# ProProject_Strain_Gauge_Paddle_2024-04-2.net
KiCad netlist of a schematic drawn in EasyEDA Pro
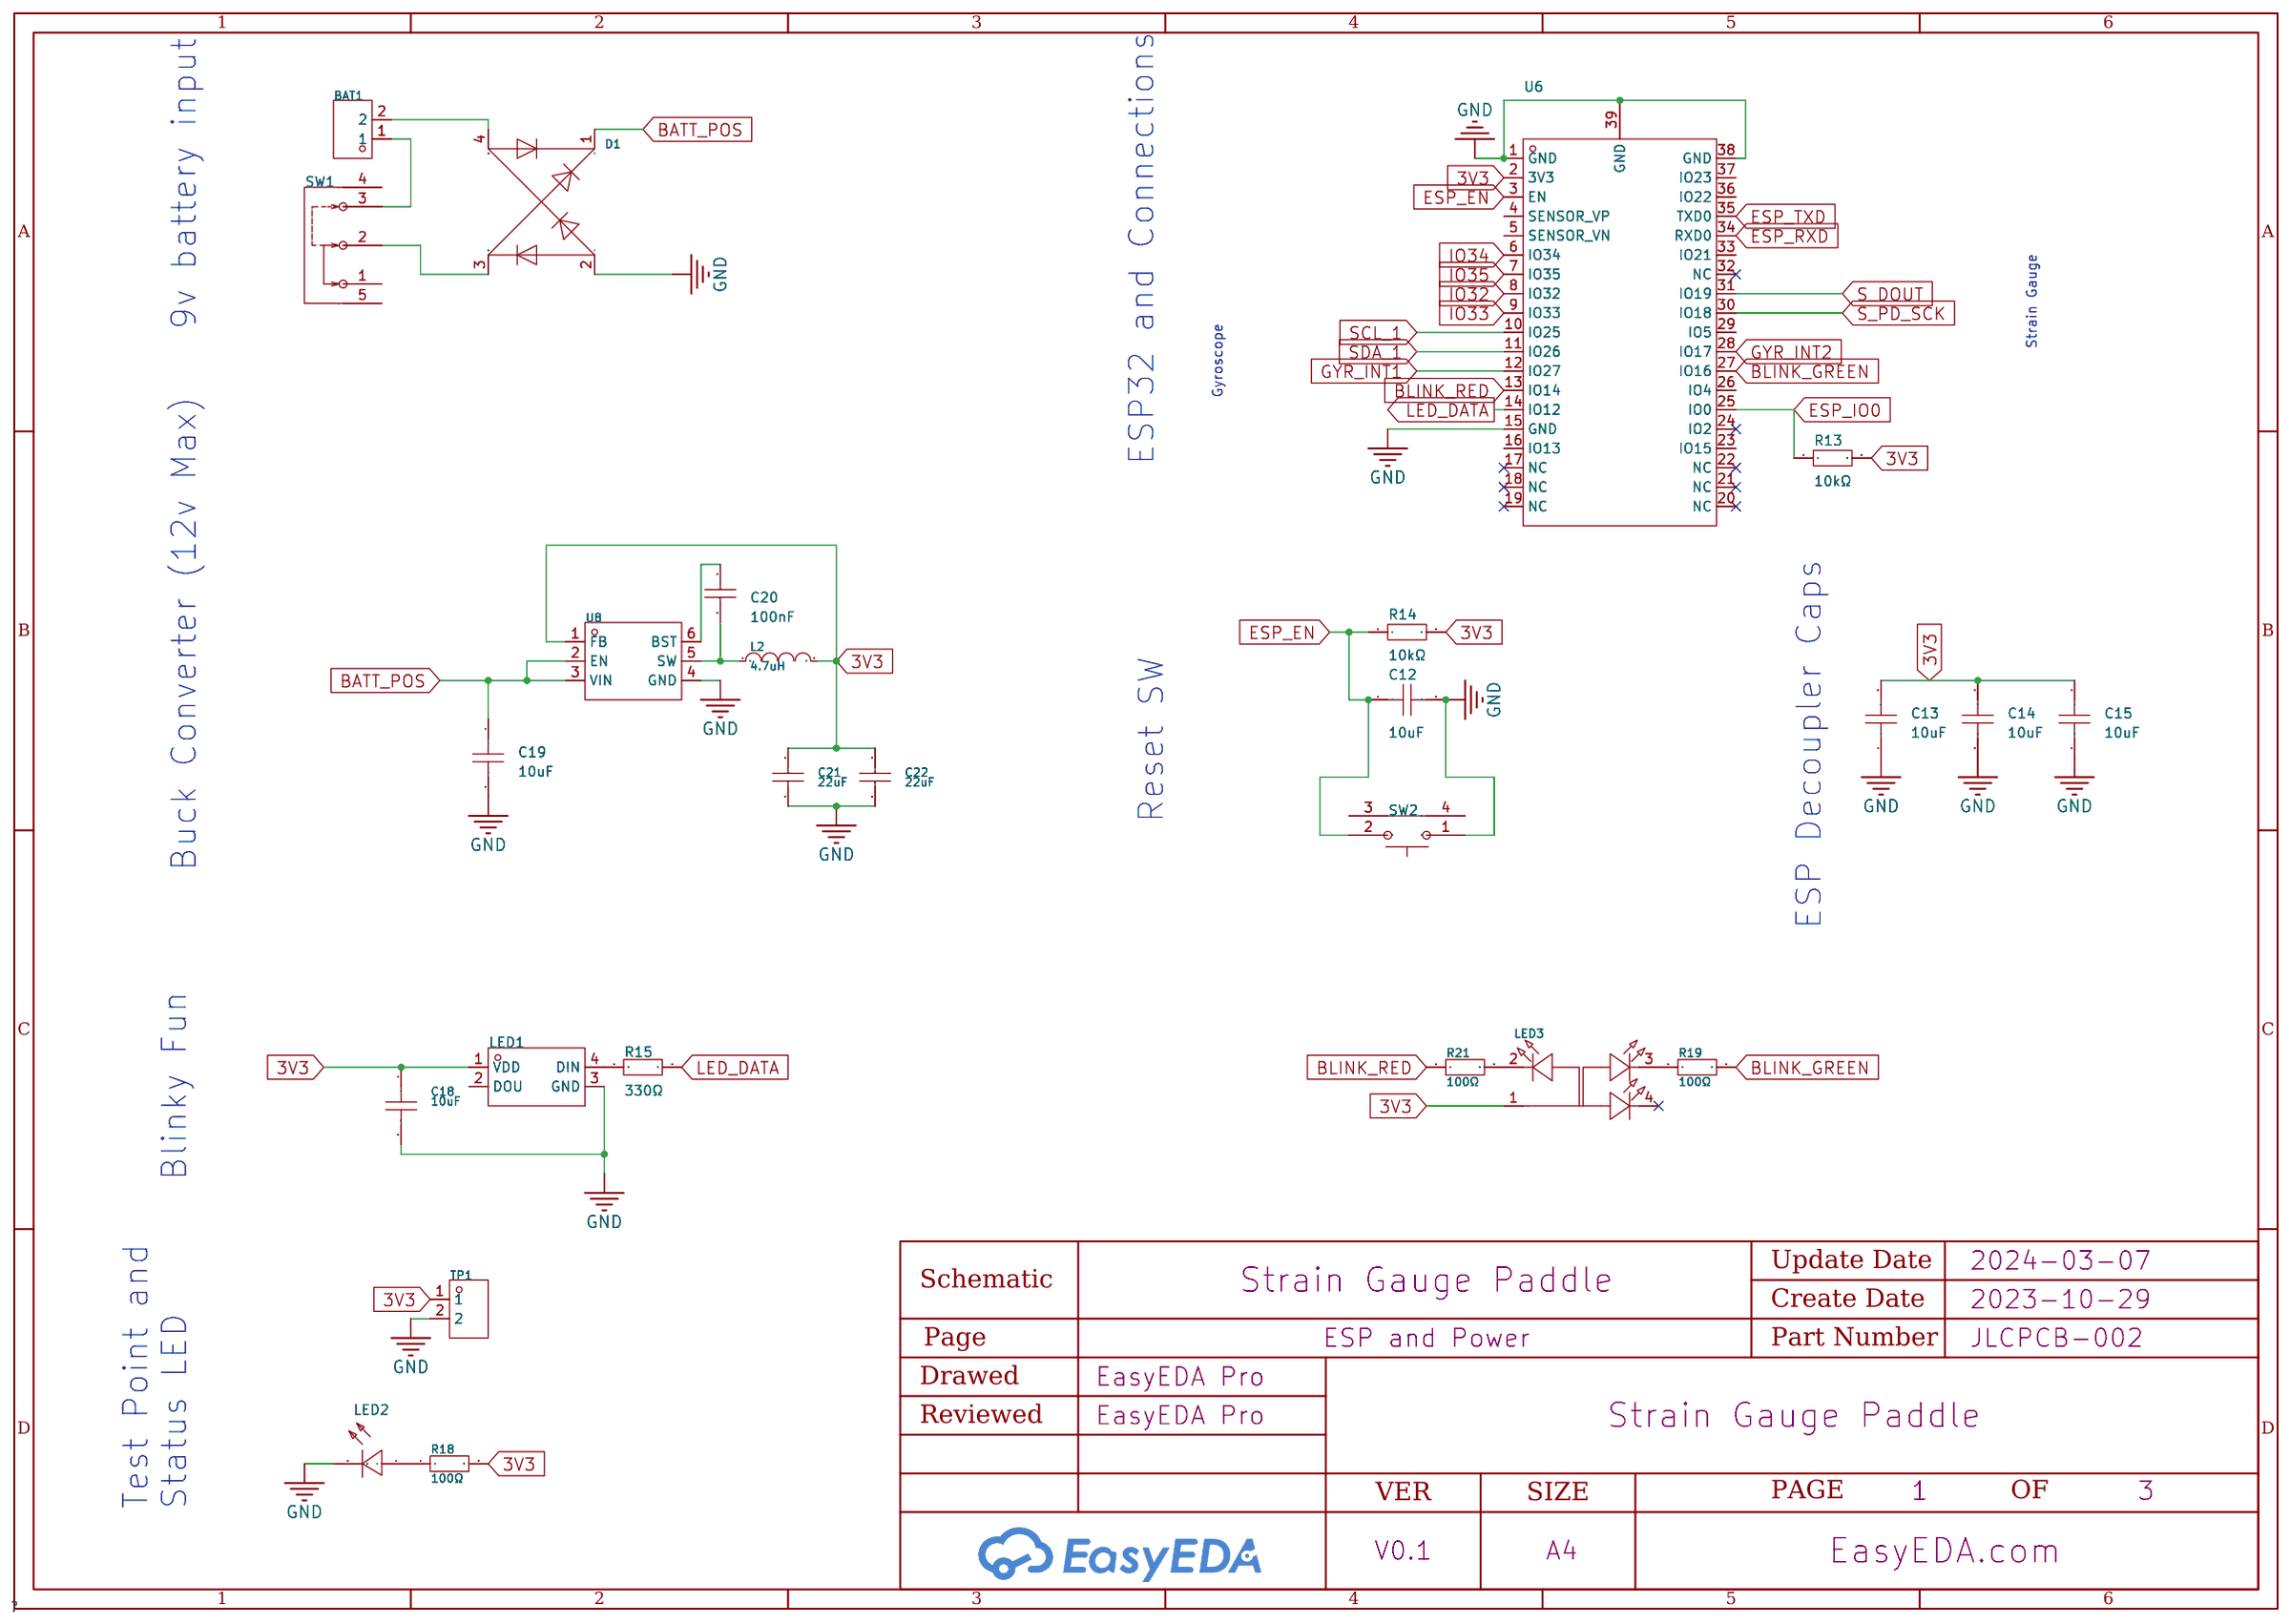
[diagram p0: ESP and Power]
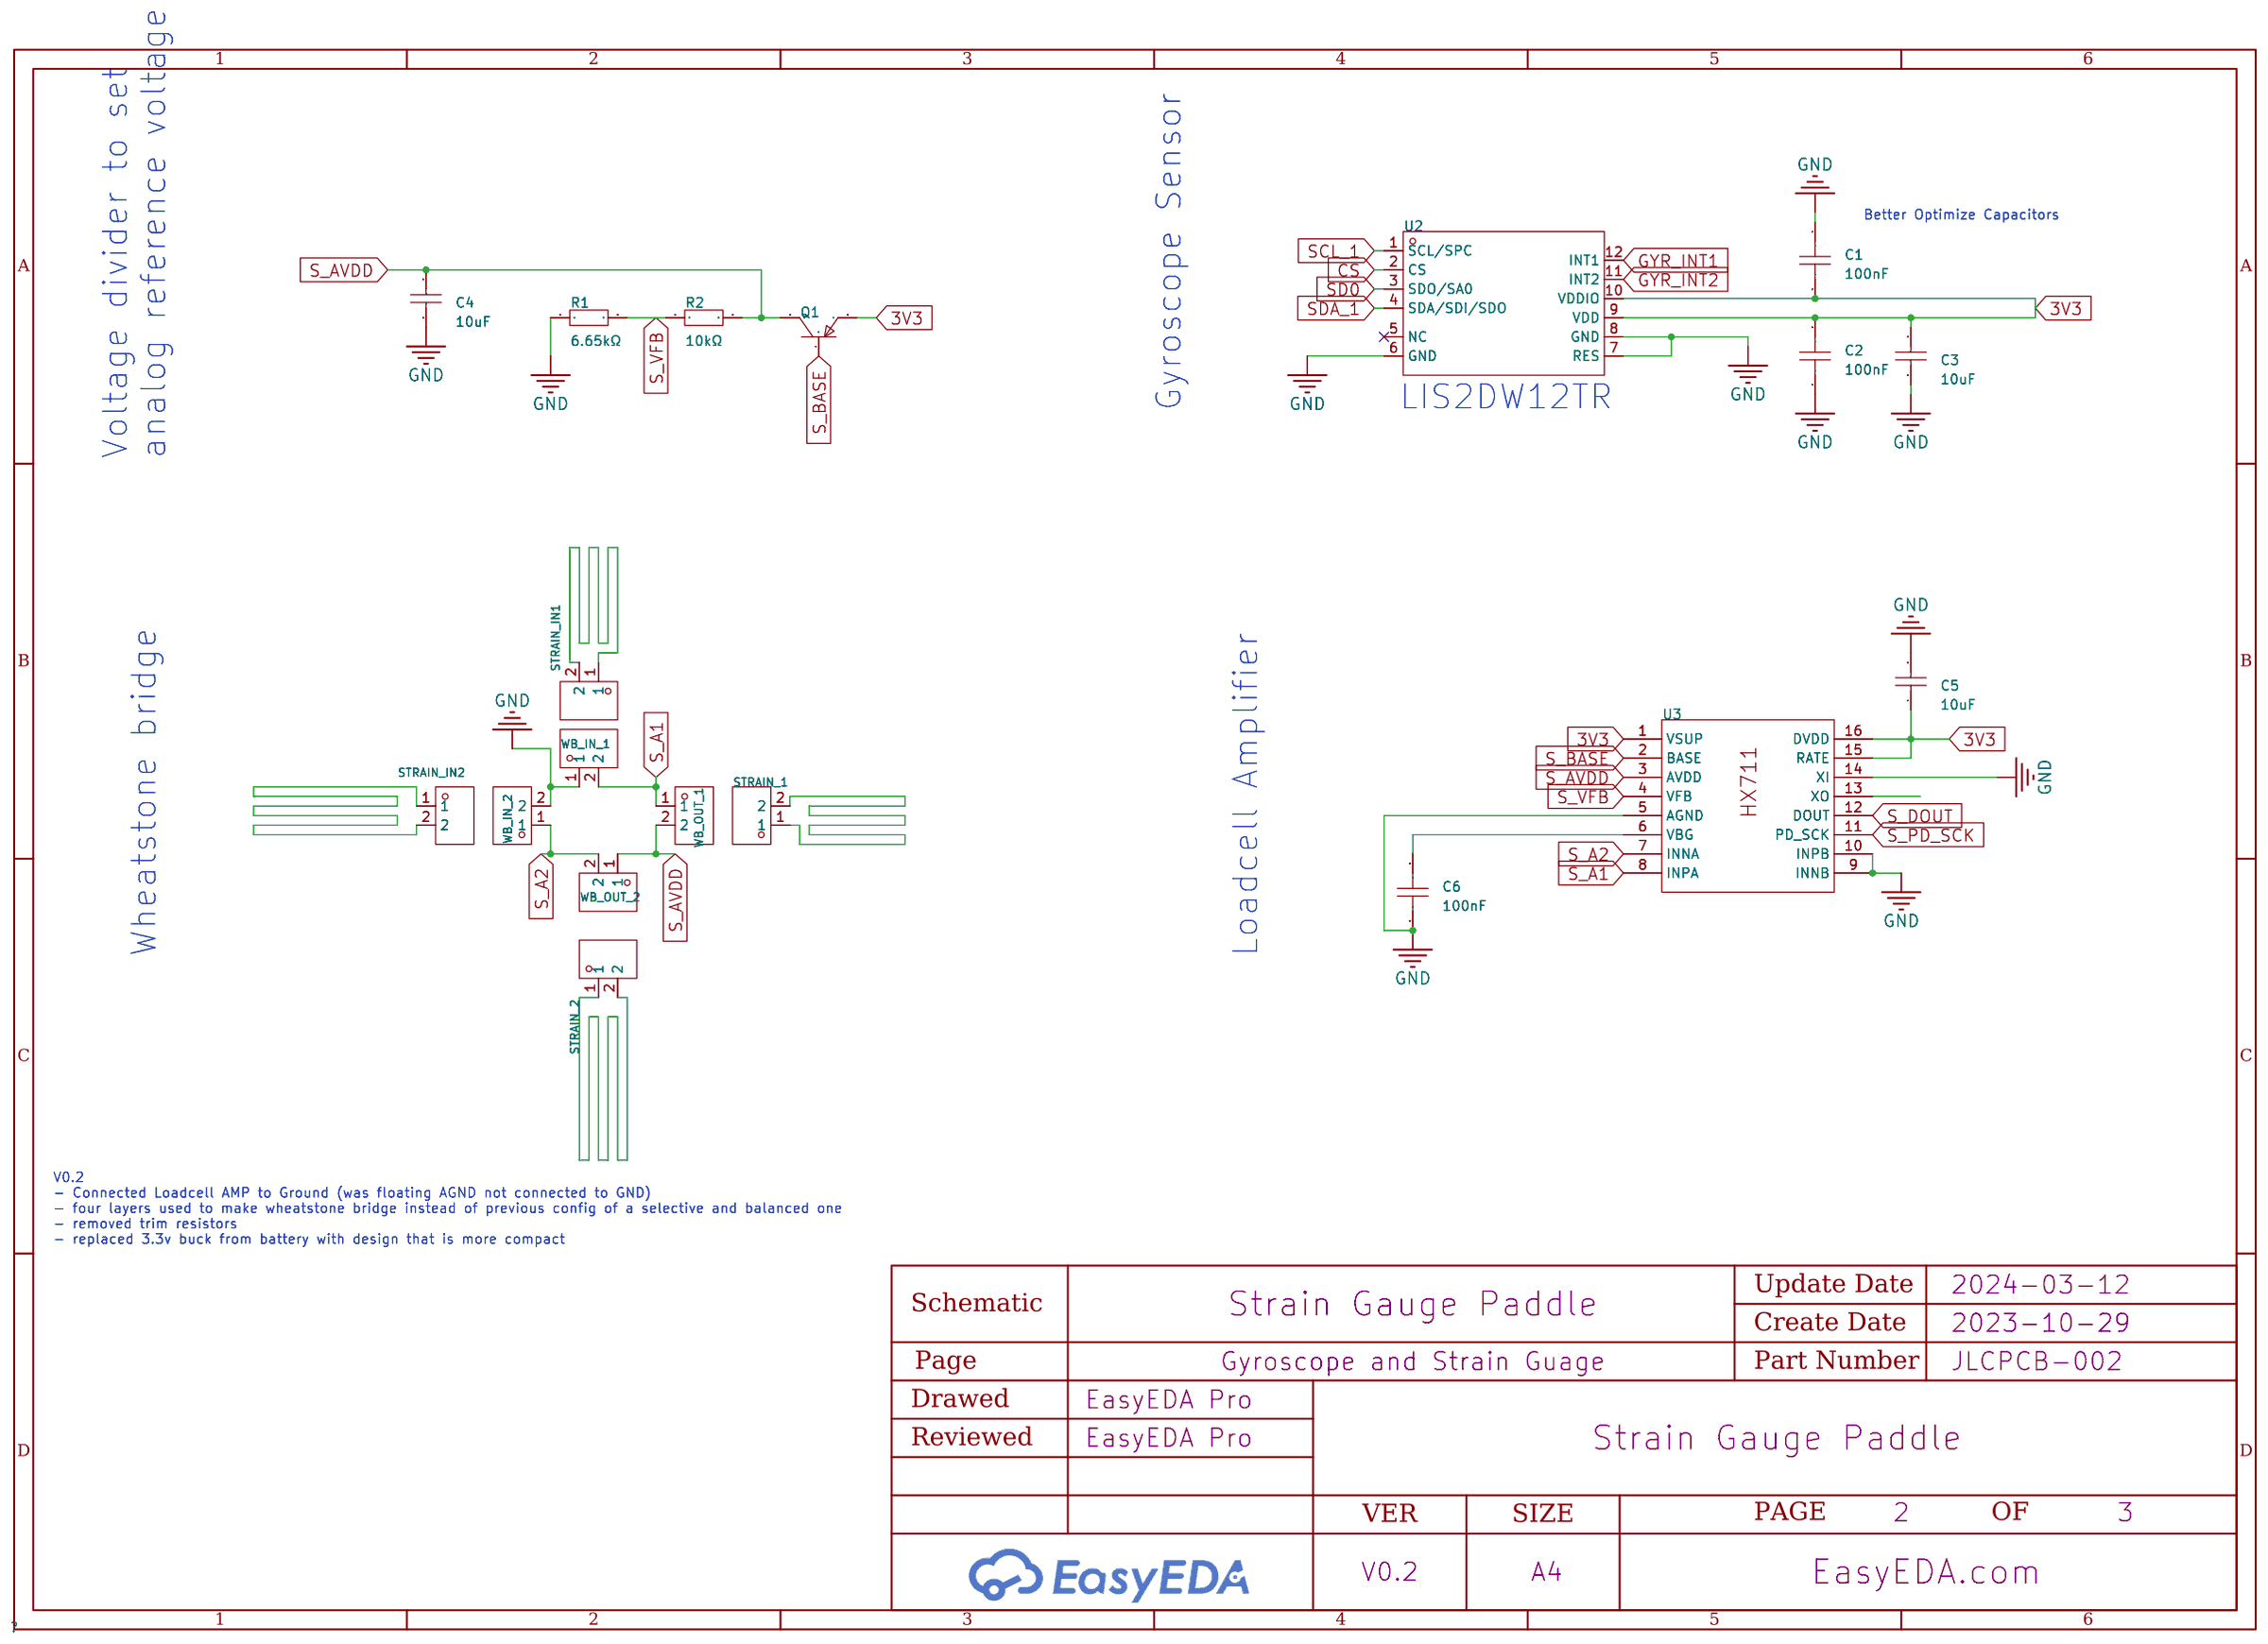
[diagram p1: Gyroscope and Strain Guage]
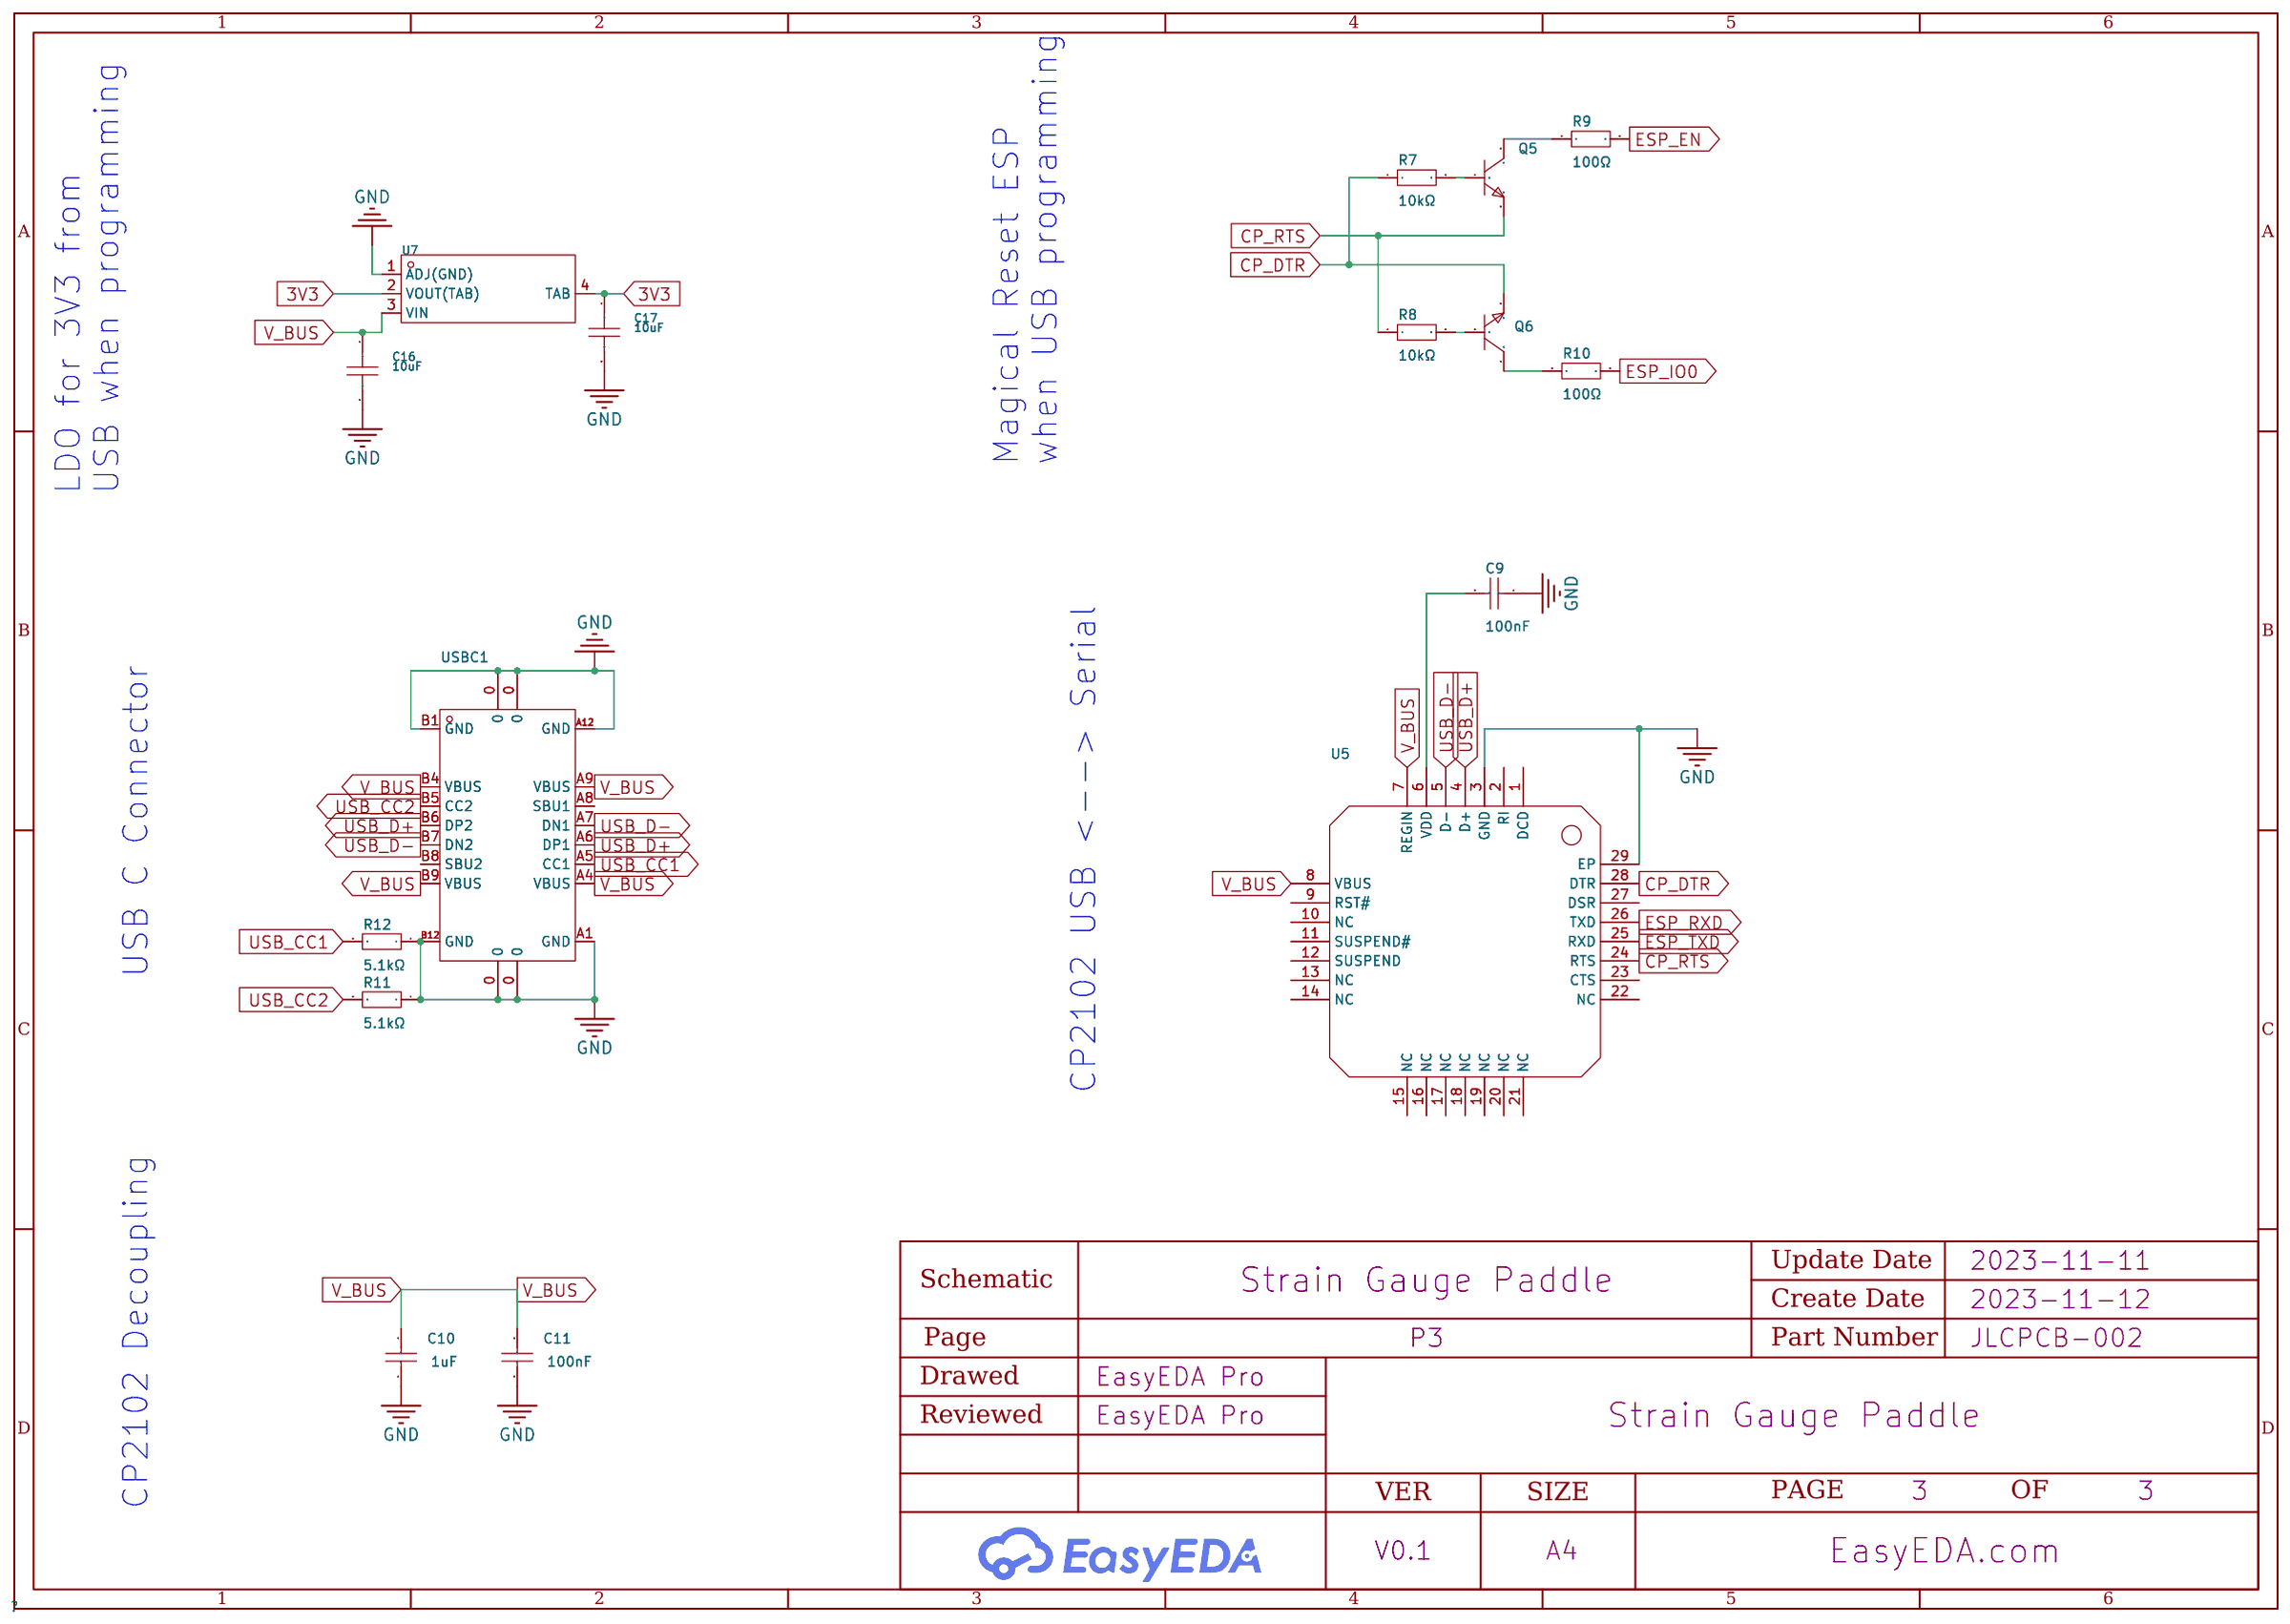
[diagram p2: Serial]

(export (version "E")
  (design (tool "Eeschema 10.0.6"))
  (components
    (comp (ref "BAT1")
      (value "PZ254V-11-02P")
      (footprint "easyedapro:HDR-TH_2P-P2.54-V-M")
      (fields (field (name "Manufacturer") "XFCN(兴飞)"))
      (libsource (lib "easyedapro") (part "PZ254V-11-02P"))
    )
    (comp (ref "C12")
      (value "10uF")
      (footprint "easyedapro:C0402")
      (description "Capacitance:10uF Tolerance:±20% Tolerance:±20% Voltage Rated:10V Temperature Coefficient:X5R")
      (fields
        (field (name "Manufacturer Part") "GRM155R61A106ME44D")
        (field (name "Manufacturer") "muRata(村田)")
      )
      (libsource (lib "easyedapro") (part "GRM155R61A106ME44D"))
    )
    (comp (ref "C13")
      (value "10uF")
      (footprint "easyedapro:C0402")
      (description "Capacitance:10uF Tolerance:±20% Tolerance:±20% Voltage Rated:10V Temperature Coefficient:X5R")
      (fields
        (field (name "Manufacturer Part") "GRM155R61A106ME44D")
        (field (name "Manufacturer") "muRata(村田)")
      )
      (libsource (lib "easyedapro") (part "GRM155R61A106ME44D"))
    )
    (comp (ref "C14")
      (value "10uF")
      (footprint "easyedapro:C0402")
      (description "Capacitance:10uF Tolerance:±20% Tolerance:±20% Voltage Rated:10V Temperature Coefficient:X5R")
      (fields
        (field (name "Manufacturer Part") "GRM155R61A106ME44D")
        (field (name "Manufacturer") "muRata(村田)")
      )
      (libsource (lib "easyedapro") (part "GRM155R61A106ME44D"))
    )
    (comp (ref "C15")
      (value "10uF")
      (footprint "easyedapro:C0402")
      (description "Capacitance:10uF Tolerance:±20% Tolerance:±20% Voltage Rated:10V Temperature Coefficient:X5R")
      (fields
        (field (name "Manufacturer Part") "GRM155R61A106ME44D")
        (field (name "Manufacturer") "muRata(村田)")
      )
      (libsource (lib "easyedapro") (part "GRM155R61A106ME44D"))
    )
    (comp (ref "C18")
      (value "10uF")
      (footprint "easyedapro:C0603")
      (fields
        (field (name "Manufacturer Part") "CL10A106MQ8NNNC")
        (field (name "Manufacturer") "SAMSUNG(三星)")
      )
      (libsource (lib "easyedapro") (part "CL10A106MQ8NNNC"))
    )
    (comp (ref "C19")
      (value "10uF")
      (footprint "easyedapro:C0603")
      (fields
        (field (name "Manufacturer Part") "CL10A106KP8NNNC")
        (field (name "Manufacturer") "SAMSUNG(三星)")
      )
      (libsource (lib "easyedapro") (part "CL10A106KP8NNNC"))
    )
    (comp (ref "C20")
      (value "100nF")
      (footprint "easyedapro:C0603")
      (fields (field (name "Manufacturer Part") "0603B104K500NT") (field (name "Manufacturer") "FH(风华)"))
      (libsource (lib "easyedapro") (part "0603B104K500NT"))
    )
    (comp (ref "C21")
      (value "22uF")
      (footprint "easyedapro:C1206")
      (fields
        (field (name "Manufacturer Part") "CL31A226KAHNNNE")
        (field (name "Manufacturer") "SAMSUNG(三星)")
      )
      (libsource (lib "easyedapro") (part "CL31A226KAHNNNE"))
    )
    (comp (ref "C22")
      (value "22uF")
      (footprint "easyedapro:C1206")
      (fields
        (field (name "Manufacturer Part") "CL31A226KAHNNNE")
        (field (name "Manufacturer") "SAMSUNG(三星)")
      )
      (libsource (lib "easyedapro") (part "CL31A226KAHNNNE"))
    )
    (comp (ref "D1")
      (value "MB10S")
      (footprint "easyedapro:MBS_L4.7-W3.8-P2.40-LS7.0-TL")
      (fields (field (name "Manufacturer") "MDD"))
      (libsource (lib "easyedapro") (part "MB10S_C2488"))
    )
    (comp (ref "L2")
      (value "4.7uH")
      (footprint "easyedapro:IND-SMD_L5.4-W5.2_FXL0530")
      (fields (field (name "Manufacturer Part") "FXL0530-4R7-M") (field (name "Manufacturer") "cjiang(长江微电)"))
      (libsource (lib "easyedapro") (part "FXL0530-4R7-M"))
    )
    (comp (ref "LED1")
      (value "XL-5050RGBC-WS2812B")
      (footprint "easyedapro:LED-SMD_4P-L5.0-W5.0-BL_XL-5050RGBC")
      (fields (field (name "Manufacturer") "XINGLIGHT(成兴光)"))
      (libsource (lib "easyedapro") (part "XL-5050RGBC-WS2812B"))
    )
    (comp (ref "LED2")
      (value "BL-HJC36G-AV-TRB")
      (footprint "easyedapro:LED0603-R-RD_AMBER")
      (fields (field (name "Manufacturer") "BrtLed(佰鸿)"))
      (libsource (lib "easyedapro") (part "BL-HJC36G-AV-TRB"))
    )
    (comp (ref "LED3")
      (value "NH-B1010RGBT-HF")
      (footprint "easyedapro:LED-ARRAY-SMD_4P-L1.0-W1.0-TR_NH-B1010RGBT")
      (fields (field (name "Manufacturer") "国星光电"))
      (libsource (lib "easyedapro") (part "NH-B1010RGBT-HF"))
    )
    (comp (ref "R13")
      (value "10kΩ")
      (footprint "easyedapro:R0402")
      (fields (field (name "Manufacturer Part") "WR04X1002FTL") (field (name "Manufacturer") "华新科(Walsin)"))
      (libsource (lib "easyedapro") (part "WR04X1002FTL"))
    )
    (comp (ref "R14")
      (value "10kΩ")
      (footprint "easyedapro:R0402")
      (fields (field (name "Manufacturer Part") "WR04X1002FTL") (field (name "Manufacturer") "华新科(Walsin)"))
      (libsource (lib "easyedapro") (part "WR04X1002FTL"))
    )
    (comp (ref "R15")
      (value "330Ω")
      (footprint "easyedapro:R0603")
      (fields
        (field (name "Manufacturer Part") "0603WAF3300T5E")
        (field (name "Manufacturer") "UNI-ROYAL(厚声)")
      )
      (libsource (lib "easyedapro") (part "0603WAF3300T5E"))
    )
    (comp (ref "R18")
      (value "100Ω")
      (footprint "easyedapro:R0603")
      (fields
        (field (name "Manufacturer Part") "0603WAF1000T5E")
        (field (name "Manufacturer") "UNI-ROYAL(厚声)")
      )
      (libsource (lib "easyedapro") (part "0603WAF1000T5E"))
    )
    (comp (ref "R19")
      (value "100Ω")
      (footprint "easyedapro:R0603")
      (fields
        (field (name "Manufacturer Part") "0603WAF1000T5E")
        (field (name "Manufacturer") "UNI-ROYAL(厚声)")
      )
      (libsource (lib "easyedapro") (part "0603WAF1000T5E"))
    )
    (comp (ref "R21")
      (value "100Ω")
      (footprint "easyedapro:R0603")
      (fields
        (field (name "Manufacturer Part") "0603WAF1000T5E")
        (field (name "Manufacturer") "UNI-ROYAL(厚声)")
      )
      (libsource (lib "easyedapro") (part "0603WAF1000T5E"))
    )
    (comp (ref "SW1")
      (value "SK12D07VG4")
      (footprint "easyedapro:SW-TH_SK12D07VG4")
      (fields (field (name "Manufacturer") "SHOU HAN(首韩)"))
      (libsource (lib "easyedapro") (part "SK12D07VG4"))
    )
    (comp (ref "SW2")
      (value "1TS003B-1400-3500A-CT")
      (footprint "easyedapro:KEY-SMD_1TS003B")
      (fields (field (name "Manufacturer") "HYP(鸿源精密)"))
      (libsource (lib "easyedapro") (part "1TS003B-1400-3500A"))
    )
    (comp (ref "TP1")
      (value "PZ254V-11-02P")
      (footprint "easyedapro:HDR-TH_2P-P2.54-V-M")
      (fields (field (name "Manufacturer") "XFCN(兴飞)"))
      (libsource (lib "easyedapro") (part "PZ254V-11-02P"))
    )
    (comp (ref "U6")
      (value "~")
      (footprint "easyedapro:WIFI-SMD_ESP32-WROOM-32E")
      (fields
        (field (name "Manufacturer Part") "ESP32-WROOM-32E(8MB)")
        (field (name "Manufacturer") "ESPRESSIF 乐鑫")
      )
      (libsource (lib "easyedapro") (part "ESP32-WROOM-32E(8MB)"))
    )
    (comp (ref "U8")
      (value "AP63203WU-7")
      (footprint "easyedapro:TSOT-26_L2.9-W1.6-P0.95-LS2.8-BL")
      (fields (field (name "Manufacturer") "DIODES(美台)"))
      (libsource (lib "easyedapro") (part "AP63203WU-7"))
    )
    (comp (ref "C1")
      (value "100nF")
      (footprint "easyedapro:C0603")
      (fields
        (field (name "Manufacturer Part") "CC0603KRX7R9BB104")
        (field (name "Manufacturer") "YAGEO(国巨)")
      )
      (libsource (lib "easyedapro") (part "CC0603KRX7R9BB104"))
    )
    (comp (ref "C2")
      (value "100nF")
      (footprint "easyedapro:C0603")
      (fields
        (field (name "Manufacturer Part") "CC0603KRX7R9BB104")
        (field (name "Manufacturer") "YAGEO(国巨)")
      )
      (libsource (lib "easyedapro") (part "CC0603KRX7R9BB104"))
    )
    (comp (ref "C3")
      (value "10uF")
      (footprint "easyedapro:C0805")
      (fields
        (field (name "Manufacturer Part") "CL21A106KAYNNNE")
        (field (name "Manufacturer") "SAMSUNG(三星)")
      )
      (libsource (lib "easyedapro") (part "CL21A106KAYNNNE"))
    )
    (comp (ref "C4")
      (value "10uF")
      (footprint "easyedapro:C0805")
      (fields
        (field (name "Manufacturer Part") "CL21A106KAYNNNE")
        (field (name "Manufacturer") "SAMSUNG(三星)")
      )
      (libsource (lib "easyedapro") (part "CL21A106KAYNNNE"))
    )
    (comp (ref "C5")
      (value "10uF")
      (footprint "easyedapro:C0805")
      (fields
        (field (name "Manufacturer Part") "CL21A106KAYNNNE")
        (field (name "Manufacturer") "SAMSUNG(三星)")
      )
      (libsource (lib "easyedapro") (part "CL21A106KAYNNNE"))
    )
    (comp (ref "C6")
      (value "100nF")
      (footprint "easyedapro:C0603")
      (fields
        (field (name "Manufacturer Part") "CC0603KRX7R9BB104")
        (field (name "Manufacturer") "YAGEO(国巨)")
      )
      (libsource (lib "easyedapro") (part "CC0603KRX7R9BB104"))
    )
    (comp (ref "Q1")
      (value "S8550")
      (footprint "easyedapro:SOT-23-3_L2.9-W1.3-P1.90-LS2.4-BR")
      (fields (field (name "Manufacturer") "YONGYUTAI(永裕泰)"))
      (libsource (lib "easyedapro") (part "S8550_C2891805"))
    )
    (comp (ref "R1")
      (value "6.65kΩ")
      (footprint "easyedapro:R0603")
      (fields
        (field (name "Manufacturer Part") "0603WAF6651T5E")
        (field (name "Manufacturer") "UNI-ROYAL(厚声)")
      )
      (libsource (lib "easyedapro") (part "0603WAF6651T5E"))
    )
    (comp (ref "R2")
      (value "10kΩ")
      (footprint "easyedapro:R0805")
      (fields
        (field (name "Manufacturer Part") "0805W8F1002T5E")
        (field (name "Manufacturer") "UNI-ROYAL(厚声)")
      )
      (libsource (lib "easyedapro") (part "0805W8F1002T5E"))
    )
    (comp (ref "STRAIN_1")
      (value "PZ254V-11-02P")
      (footprint "easyedapro:HDR-TH_2P-P2.54-V-M")
      (fields (field (name "Manufacturer") "XFCN(兴飞)"))
      (libsource (lib "easyedapro") (part "PZ254V-11-02P"))
    )
    (comp (ref "STRAIN_2")
      (value "PZ254V-11-02P")
      (footprint "easyedapro:HDR-TH_2P-P2.54-V-M")
      (fields (field (name "Manufacturer") "XFCN(兴飞)"))
      (libsource (lib "easyedapro") (part "PZ254V-11-02P"))
    )
    (comp (ref "STRAIN_IN1")
      (value "PZ254V-11-02P")
      (footprint "easyedapro:HDR-TH_2P-P2.54-V-M")
      (fields (field (name "Manufacturer") "XFCN(兴飞)"))
      (libsource (lib "easyedapro") (part "PZ254V-11-02P"))
    )
    (comp (ref "STRAIN_IN2")
      (value "PZ254V-11-02P")
      (footprint "easyedapro:HDR-TH_2P-P2.54-V-M")
      (fields (field (name "Manufacturer") "XFCN(兴飞)"))
      (libsource (lib "easyedapro") (part "PZ254V-11-02P"))
    )
    (comp (ref "U2")
      (value "LIS2DW12TR")
      (footprint "easyedapro:LGA-12_L2.0-W2.0-P0.50-BL")
      (fields (field (name "Manufacturer") "ST(意法半导体)"))
      (libsource (lib "easyedapro") (part "LIS2DW12TR"))
    )
    (comp (ref "U3")
      (value "HX711")
      (footprint "easyedapro:SOP-16_L10.0-W3.9-P1.27-LS6.0-BL")
      (fields (field (name "Manufacturer") "AVIA(海芯科技)"))
      (libsource (lib "easyedapro") (part "HX711"))
    )
    (comp (ref "WB_IN_1")
      (value "PZ254V-11-02P")
      (footprint "easyedapro:HDR-TH_2P-P2.54-V-M")
      (fields (field (name "Manufacturer") "XFCN(兴飞)"))
      (libsource (lib "easyedapro") (part "PZ254V-11-02P"))
    )
    (comp (ref "WB_IN_2")
      (value "PZ254V-11-02P")
      (footprint "easyedapro:HDR-TH_2P-P2.54-V-M")
      (fields (field (name "Manufacturer") "XFCN(兴飞)"))
      (libsource (lib "easyedapro") (part "PZ254V-11-02P"))
    )
    (comp (ref "WB_OUT_1")
      (value "PZ254V-11-02P")
      (footprint "easyedapro:HDR-TH_2P-P2.54-V-M")
      (fields (field (name "Manufacturer") "XFCN(兴飞)"))
      (libsource (lib "easyedapro") (part "PZ254V-11-02P"))
    )
    (comp (ref "WB_OUT_2")
      (value "PZ254V-11-02P")
      (footprint "easyedapro:HDR-TH_2P-P2.54-V-M")
      (fields (field (name "Manufacturer") "XFCN(兴飞)"))
      (libsource (lib "easyedapro") (part "PZ254V-11-02P"))
    )
    (comp (ref "C9")
      (value "100nF")
      (footprint "easyedapro:C0402")
      (description "Capacitance:100nF Tolerance:±10% Tolerance:±10% Voltage Rated:25V Temperature Coefficient:X5R")
      (fields (field (name "Manufacturer Part") "0402X104K250CT") (field (name "Manufacturer") "华新科(Walsin)"))
      (libsource (lib "easyedapro") (part "0402X104K250CT"))
    )
    (comp (ref "C10")
      (value "1uF")
      (footprint "easyedapro:C0402")
      (description "Capacitance:1uF Tolerance:±10% Tolerance:±10% Voltage Rated:25V Temperature Coefficient:X5R")
      (fields
        (field (name "Manufacturer Part") "GRM155R61E105KA12D")
        (field (name "Manufacturer") "muRata(村田)")
      )
      (libsource (lib "easyedapro") (part "GRM155R61E105KA12D"))
    )
    (comp (ref "C11")
      (value "100nF")
      (footprint "easyedapro:C0402")
      (description "Capacitance:100nF Tolerance:±10% Tolerance:±10% Voltage Rated:25V Temperature Coefficient:X5R")
      (fields (field (name "Manufacturer Part") "0402X104K250CT") (field (name "Manufacturer") "华新科(Walsin)"))
      (libsource (lib "easyedapro") (part "0402X104K250CT"))
    )
    (comp (ref "C16")
      (value "10uF")
      (footprint "easyedapro:C0603")
      (fields
        (field (name "Manufacturer Part") "CL10A106MQ8NNNC")
        (field (name "Manufacturer") "SAMSUNG(三星)")
      )
      (libsource (lib "easyedapro") (part "CL10A106MQ8NNNC"))
    )
    (comp (ref "C17")
      (value "10uF")
      (footprint "easyedapro:C0603")
      (fields
        (field (name "Manufacturer Part") "CL10A106MQ8NNNC")
        (field (name "Manufacturer") "SAMSUNG(三星)")
      )
      (libsource (lib "easyedapro") (part "CL10A106MQ8NNNC"))
    )
    (comp (ref "Q5")
      (value "~")
      (footprint "easyedapro:SOT-23-3_L2.9-W1.3-P1.90-LS2.4-BR")
      (fields (field (name "Manufacturer Part") "BC817") (field (name "Manufacturer") "CJ（江苏长电/长晶）"))
      (libsource (lib "easyedapro") (part "BC817-16 6A"))
    )
    (comp (ref "Q6")
      (value "~")
      (footprint "easyedapro:SOT-23-3_L2.9-W1.3-P1.90-LS2.4-BR")
      (fields (field (name "Manufacturer Part") "BC817") (field (name "Manufacturer") "CJ（江苏长电/长晶）"))
      (libsource (lib "easyedapro") (part "BC817-16 6A"))
    )
    (comp (ref "R7")
      (value "10kΩ")
      (footprint "easyedapro:R0402")
      (fields (field (name "Manufacturer Part") "WR04X1002FTL") (field (name "Manufacturer") "华新科(Walsin)"))
      (libsource (lib "easyedapro") (part "WR04X1002FTL"))
    )
    (comp (ref "R8")
      (value "10kΩ")
      (footprint "easyedapro:R0402")
      (fields (field (name "Manufacturer Part") "WR04X1002FTL") (field (name "Manufacturer") "华新科(Walsin)"))
      (libsource (lib "easyedapro") (part "WR04X1002FTL"))
    )
    (comp (ref "R9")
      (value "100Ω")
      (footprint "easyedapro:R0402")
      (fields (field (name "Manufacturer Part") "AECR0402F100RK9") (field (name "Manufacturer") "RESI(开步睿思）"))
      (libsource (lib "easyedapro") (part "AECR0402F100RK9"))
    )
    (comp (ref "R10")
      (value "100Ω")
      (footprint "easyedapro:R0402")
      (fields (field (name "Manufacturer Part") "AECR0402F100RK9") (field (name "Manufacturer") "RESI(开步睿思）"))
      (libsource (lib "easyedapro") (part "AECR0402F100RK9"))
    )
    (comp (ref "R11")
      (value "5.1kΩ")
      (footprint "easyedapro:R0402")
      (fields (field (name "Manufacturer Part") "ERJ2RKF5101X") (field (name "Manufacturer") "PANASONIC(松下)"))
      (libsource (lib "easyedapro") (part "ERJ2RKF5101X"))
    )
    (comp (ref "R12")
      (value "5.1kΩ")
      (footprint "easyedapro:R0402")
      (fields (field (name "Manufacturer Part") "ERJ2RKF5101X") (field (name "Manufacturer") "PANASONIC(松下)"))
      (libsource (lib "easyedapro") (part "ERJ2RKF5101X"))
    )
    (comp (ref "U5")
      (value "~")
      (footprint "easyedapro:WQFN-28_L5.0-W5.0-P0.50-BL-EP3.2")
      (fields
        (field (name "Manufacturer Part") "CP2102-GMR")
        (field (name "Manufacturer") "SILICON LABS(芯科)")
      )
      (libsource (lib "easyedapro") (part "CP2102-GMR"))
    )
    (comp (ref "U7")
      (value "AMS1117-3.3")
      (footprint "easyedapro:SOT-223-4_L6.5-W3.5-P2.30-LS7.0-BR")
      (fields (field (name "Manufacturer") "UMW(友台半导体)"))
      (libsource (lib "easyedapro") (part "AMS1117-3.3_C347222"))
    )
    (comp (ref "USBC1")
      (value "~")
      (footprint "easyedapro:USB-C_SMD-TYPE-C-31-M-12")
      (fields (field (name "Manufacturer Part") "TYPE-C-31-M-12") (field (name "Manufacturer") "韩国韩荣"))
      (libsource (lib "easyedapro") (part "TYPE-C-31-M-12"))
    )
  )
  (nets
    (net (code "1") (name "3V3") (class "Default")
      (node (ref "C1") (pin "2") (pinfunction "2_2") (pintype "input"))
      (node (ref "C13") (pin "2") (pinfunction "2_2") (pintype "input"))
      (node (ref "C14") (pin "2") (pinfunction "2_2") (pintype "input"))
      (node (ref "C15") (pin "2") (pinfunction "2_2") (pintype "input"))
      (node (ref "C17") (pin "1") (pinfunction "1_1") (pintype "input"))
      (node (ref "C18") (pin "1") (pinfunction "1_1") (pintype "input"))
      (node (ref "C2") (pin "2") (pinfunction "2_2") (pintype "input"))
      (node (ref "C21") (pin "1") (pinfunction "1_1") (pintype "input"))
      (node (ref "C22") (pin "1") (pinfunction "1_1") (pintype "input"))
      (node (ref "C3") (pin "2") (pinfunction "2_2") (pintype "input"))
      (node (ref "C5") (pin "1") (pinfunction "1_1") (pintype "input"))
      (node (ref "L2") (pin "2") (pinfunction "2_2") (pintype "input"))
      (node (ref "LED1") (pin "1") (pinfunction "VDD_1") (pintype "input"))
      (node (ref "LED3") (pin "1") (pinfunction "+_1") (pintype "input"))
      (node (ref "Q1") (pin "2") (pinfunction "E_2") (pintype "input"))
      (node (ref "R13") (pin "2") (pinfunction "2_2") (pintype "input"))
      (node (ref "R14") (pin "2") (pinfunction "2_2") (pintype "input"))
      (node (ref "R18") (pin "2") (pinfunction "2_2") (pintype "input"))
      (node (ref "TP1") (pin "1") (pinfunction "1_1") (pintype "input"))
      (node (ref "U2") (pin "10") (pinfunction "VDDIO_10") (pintype "input"))
      (node (ref "U2") (pin "9") (pinfunction "VDD_9") (pintype "input"))
      (node (ref "U3") (pin "1") (pinfunction "VSUP_1") (pintype "input"))
      (node (ref "U3") (pin "15") (pinfunction "RATE_15") (pintype "input"))
      (node (ref "U3") (pin "16") (pinfunction "DVDD_16") (pintype "input"))
      (node (ref "U6") (pin "2") (pinfunction "3V3_2") (pintype "input"))
      (node (ref "U7") (pin "2") (pinfunction "VOUT(TAB)_2") (pintype "input"))
      (node (ref "U7") (pin "4") (pinfunction "TAB_4") (pintype "input"))
      (node (ref "U8") (pin "1") (pinfunction "FB_1") (pintype "input"))
    )
    (net (code "2") (name "BATT_POS") (class "Default")
      (node (ref "C19") (pin "1") (pinfunction "1_1") (pintype "input"))
      (node (ref "D1") (pin "1") (pinfunction "+_1") (pintype "input"))
      (node (ref "U8") (pin "2") (pinfunction "EN_2") (pintype "input"))
      (node (ref "U8") (pin "3") (pinfunction "VIN_3") (pintype "input"))
    )
    (net (code "3") (name "BLINK_GREEN") (class "Default")
      (node (ref "R19") (pin "2") (pinfunction "2_2") (pintype "input"))
      (node (ref "U6") (pin "27") (pinfunction "IO16_27") (pintype "input"))
    )
    (net (code "4") (name "BLINK_RED") (class "Default")
      (node (ref "R21") (pin "1") (pinfunction "1_1") (pintype "input"))
      (node (ref "U6") (pin "13") (pinfunction "IO14_13") (pintype "input"))
    )
    (net (code "5") (name "CP_DTR") (class "Default")
      (node (ref "Q6") (pin "2") (pinfunction "E_2") (pintype "input"))
      (node (ref "R7") (pin "1") (pinfunction "1_1") (pintype "input"))
      (node (ref "U5") (pin "28") (pinfunction "DTR_28") (pintype "input"))
    )
    (net (code "6") (name "CP_RTS") (class "Default")
      (node (ref "Q5") (pin "2") (pinfunction "E_2") (pintype "input"))
      (node (ref "R8") (pin "1") (pinfunction "1_1") (pintype "input"))
      (node (ref "U5") (pin "24") (pinfunction "RTS_24") (pintype "input"))
    )
    (net (code "7") (name "CS") (class "Default")
      (node (ref "U2") (pin "2") (pinfunction "CS_2") (pintype "input"))
    )
    (net (code "8") (name "ESP_EN") (class "Default")
      (node (ref "C12") (pin "1") (pinfunction "1_1") (pintype "input"))
      (node (ref "R14") (pin "1") (pinfunction "1_1") (pintype "input"))
      (node (ref "R9") (pin "2") (pinfunction "2_2") (pintype "input"))
      (node (ref "SW2") (pin "2") (pinfunction "2_2") (pintype "input"))
      (node (ref "U6") (pin "3") (pinfunction "EN_3") (pintype "input"))
    )
    (net (code "9") (name "ESP_IO0") (class "Default")
      (node (ref "R10") (pin "2") (pinfunction "2_2") (pintype "input"))
      (node (ref "R13") (pin "1") (pinfunction "1_1") (pintype "input"))
      (node (ref "U6") (pin "25") (pinfunction "IO0_25") (pintype "input"))
    )
    (net (code "10") (name "ESP_RXD") (class "Default")
      (node (ref "U5") (pin "26") (pinfunction "TXD_26") (pintype "input"))
      (node (ref "U6") (pin "34") (pinfunction "RXD0_34") (pintype "input"))
    )
    (net (code "11") (name "ESP_TXD") (class "Default")
      (node (ref "U5") (pin "25") (pinfunction "RXD_25") (pintype "input"))
      (node (ref "U6") (pin "35") (pinfunction "TXD0_35") (pintype "input"))
    )
    (net (code "12") (name "GND") (class "Default")
      (node (ref "C1") (pin "1") (pinfunction "1_1") (pintype "input"))
      (node (ref "C10") (pin "1") (pinfunction "1_1") (pintype "input"))
      (node (ref "C11") (pin "1") (pinfunction "1_1") (pintype "input"))
      (node (ref "C12") (pin "2") (pinfunction "2_2") (pintype "input"))
      (node (ref "C13") (pin "1") (pinfunction "1_1") (pintype "input"))
      (node (ref "C14") (pin "1") (pinfunction "1_1") (pintype "input"))
      (node (ref "C15") (pin "1") (pinfunction "1_1") (pintype "input"))
      (node (ref "C16") (pin "2") (pinfunction "2_2") (pintype "input"))
      (node (ref "C17") (pin "2") (pinfunction "2_2") (pintype "input"))
      (node (ref "C18") (pin "2") (pinfunction "2_2") (pintype "input"))
      (node (ref "C19") (pin "2") (pinfunction "2_2") (pintype "input"))
      (node (ref "C2") (pin "1") (pinfunction "1_1") (pintype "input"))
      (node (ref "C21") (pin "2") (pinfunction "2_2") (pintype "input"))
      (node (ref "C22") (pin "2") (pinfunction "2_2") (pintype "input"))
      (node (ref "C3") (pin "1") (pinfunction "1_1") (pintype "input"))
      (node (ref "C4") (pin "1") (pinfunction "1_1") (pintype "input"))
      (node (ref "C5") (pin "2") (pinfunction "2_2") (pintype "input"))
      (node (ref "C6") (pin "1") (pinfunction "1_1") (pintype "input"))
      (node (ref "C9") (pin "1") (pinfunction "1_1") (pintype "input"))
      (node (ref "D1") (pin "2") (pinfunction "-_2") (pintype "input"))
      (node (ref "LED1") (pin "3") (pinfunction "GND_3") (pintype "input"))
      (node (ref "LED2") (pin "2") (pinfunction "C_2") (pintype "input"))
      (node (ref "R1") (pin "1") (pinfunction "1_1") (pintype "input"))
      (node (ref "R11") (pin "1") (pinfunction "1_1") (pintype "input"))
      (node (ref "R12") (pin "1") (pinfunction "1_1") (pintype "input"))
      (node (ref "SW2") (pin "1") (pinfunction "1_1") (pintype "input"))
      (node (ref "TP1") (pin "2") (pinfunction "2_2") (pintype "input"))
      (node (ref "U2") (pin "6") (pinfunction "GND_6") (pintype "input"))
      (node (ref "U2") (pin "7") (pinfunction "RES_7") (pintype "input"))
      (node (ref "U2") (pin "8") (pinfunction "GND_8") (pintype "input"))
      (node (ref "U3") (pin "10") (pinfunction "INPB_10") (pintype "input"))
      (node (ref "U3") (pin "14") (pinfunction "XI_14") (pintype "input"))
      (node (ref "U3") (pin "5") (pinfunction "AGND_5") (pintype "input"))
      (node (ref "U3") (pin "9") (pinfunction "INNB_9") (pintype "input"))
      (node (ref "U5") (pin "29") (pinfunction "EP_29") (pintype "input"))
      (node (ref "U5") (pin "3") (pinfunction "GND_3") (pintype "input"))
      (node (ref "U6") (pin "1") (pinfunction "GND_1") (pintype "input"))
      (node (ref "U6") (pin "15") (pinfunction "GND_15") (pintype "input"))
      (node (ref "U6") (pin "38") (pinfunction "GND_38") (pintype "input"))
      (node (ref "U6") (pin "39") (pinfunction "GND_39") (pintype "input"))
      (node (ref "U7") (pin "1") (pinfunction "ADJ(GND)_1") (pintype "input"))
      (node (ref "U8") (pin "4") (pinfunction "GND_4") (pintype "input"))
      (node (ref "USBC1") (pin "0") (pinfunction "0_0") (pintype "input"))
      (node (ref "USBC1") (pin "A1") (pinfunction "GND_A1") (pintype "input"))
      (node (ref "USBC1") (pin "A12") (pinfunction "GND_A12") (pintype "input"))
      (node (ref "USBC1") (pin "B1") (pinfunction "GND_B1") (pintype "input"))
      (node (ref "USBC1") (pin "B12") (pinfunction "GND_B12") (pintype "input"))
      (node (ref "WB_IN_1") (pin "1") (pinfunction "1_1") (pintype "input"))
      (node (ref "WB_IN_2") (pin "2") (pinfunction "2_2") (pintype "input"))
    )
    (net (code "13") (name "GYR_INT1") (class "Default")
      (node (ref "U2") (pin "12") (pinfunction "INT1_12") (pintype "input"))
      (node (ref "U6") (pin "12") (pinfunction "IO27_12") (pintype "input"))
    )
    (net (code "14") (name "GYR_INT2") (class "Default")
      (node (ref "U2") (pin "11") (pinfunction "INT2_11") (pintype "input"))
      (node (ref "U6") (pin "28") (pinfunction "IO17_28") (pintype "input"))
    )
    (net (code "15") (name "IO32") (class "Default")
      (node (ref "U6") (pin "8") (pinfunction "IO32_8") (pintype "input"))
    )
    (net (code "16") (name "IO33") (class "Default")
      (node (ref "U6") (pin "9") (pinfunction "IO33_9") (pintype "input"))
    )
    (net (code "17") (name "IO34") (class "Default")
      (node (ref "U6") (pin "6") (pinfunction "IO34_6") (pintype "input"))
    )
    (net (code "18") (name "IO35") (class "Default")
      (node (ref "U6") (pin "7") (pinfunction "IO35_7") (pintype "input"))
    )
    (net (code "19") (name "LED_DATA") (class "Default")
      (node (ref "R15") (pin "2") (pinfunction "2_2") (pintype "input"))
      (node (ref "U6") (pin "14") (pinfunction "IO12_14") (pintype "input"))
    )
    (net (code "20") (name "Net-(BAT1-Pad1)") (class "Default")
      (node (ref "BAT1") (pin "1") (pinfunction "1_1") (pintype "input"))
      (node (ref "SW1") (pin "3") (pinfunction "3_3") (pintype "input"))
    )
    (net (code "21") (name "Net-(D1-C1)") (class "Default")
      (node (ref "BAT1") (pin "2") (pinfunction "2_2") (pintype "input"))
      (node (ref "D1") (pin "4") (pinfunction "C1_4") (pintype "input"))
    )
    (net (code "22") (name "Net-(D1-C2)") (class "Default")
      (node (ref "D1") (pin "3") (pinfunction "C2_3") (pintype "input"))
      (node (ref "SW1") (pin "2") (pinfunction "2_2") (pintype "input"))
    )
    (net (code "23") (name "Net-(LED1-DIN)") (class "Default")
      (node (ref "LED1") (pin "4") (pinfunction "DIN_4") (pintype "input"))
      (node (ref "R15") (pin "1") (pinfunction "1_1") (pintype "input"))
    )
    (net (code "24") (name "Net-(LED2-A)") (class "Default")
      (node (ref "LED2") (pin "1") (pinfunction "A_1") (pintype "input"))
      (node (ref "R18") (pin "1") (pinfunction "1_1") (pintype "input"))
    )
    (net (code "25") (name "Net-(LED3---Pad2)") (class "Default")
      (node (ref "LED3") (pin "2") (pinfunction "-_2") (pintype "input"))
      (node (ref "R21") (pin "2") (pinfunction "2_2") (pintype "input"))
    )
    (net (code "26") (name "Net-(LED3---Pad3)") (class "Default")
      (node (ref "LED3") (pin "3") (pinfunction "-_3") (pintype "input"))
      (node (ref "R19") (pin "1") (pinfunction "1_1") (pintype "input"))
    )
    (net (code "27") (name "Net-(Q5-B)") (class "Default")
      (node (ref "Q5") (pin "1") (pinfunction "B_1") (pintype "input"))
      (node (ref "R7") (pin "2") (pinfunction "2_2") (pintype "input"))
    )
    (net (code "28") (name "Net-(Q5-C)") (class "Default")
      (node (ref "Q5") (pin "3") (pinfunction "C_3") (pintype "input"))
      (node (ref "R9") (pin "1") (pinfunction "1_1") (pintype "input"))
    )
    (net (code "29") (name "Net-(Q6-B)") (class "Default")
      (node (ref "Q6") (pin "1") (pinfunction "B_1") (pintype "input"))
      (node (ref "R8") (pin "2") (pinfunction "2_2") (pintype "input"))
    )
    (net (code "30") (name "Net-(Q6-C)") (class "Default")
      (node (ref "Q6") (pin "3") (pinfunction "C_3") (pintype "input"))
      (node (ref "R10") (pin "1") (pinfunction "1_1") (pintype "input"))
    )
    (net (code "31") (name "Net-(STRAIN_1-Pad1)") (class "Default")
      (node (ref "STRAIN_1") (pin "1") (pinfunction "1_1") (pintype "input"))
      (node (ref "STRAIN_1") (pin "2") (pinfunction "2_2") (pintype "input"))
    )
    (net (code "32") (name "Net-(STRAIN_2-Pad1)") (class "Default")
      (node (ref "STRAIN_2") (pin "1") (pinfunction "1_1") (pintype "input"))
      (node (ref "STRAIN_2") (pin "2") (pinfunction "2_2") (pintype "input"))
    )
    (net (code "33") (name "Net-(STRAIN_IN1-Pad1)") (class "Default")
      (node (ref "STRAIN_IN1") (pin "1") (pinfunction "1_1") (pintype "input"))
      (node (ref "STRAIN_IN1") (pin "2") (pinfunction "2_2") (pintype "input"))
    )
    (net (code "34") (name "Net-(STRAIN_IN2-Pad1)") (class "Default")
      (node (ref "STRAIN_IN2") (pin "1") (pinfunction "1_1") (pintype "input"))
      (node (ref "STRAIN_IN2") (pin "2") (pinfunction "2_2") (pintype "input"))
    )
    (net (code "35") (name "Net-(U3-VBG)") (class "Default")
      (node (ref "C6") (pin "2") (pinfunction "2_2") (pintype "input"))
      (node (ref "U3") (pin "6") (pinfunction "VBG_6") (pintype "input"))
    )
    (net (code "36") (name "Net-(U5-VDD)") (class "Default")
      (node (ref "C9") (pin "2") (pinfunction "2_2") (pintype "input"))
      (node (ref "U5") (pin "6") (pinfunction "VDD_6") (pintype "input"))
    )
    (net (code "37") (name "Net-(U8-BST)") (class "Default")
      (node (ref "C20") (pin "1") (pinfunction "1_1") (pintype "input"))
      (node (ref "U8") (pin "6") (pinfunction "BST_6") (pintype "input"))
    )
    (net (code "38") (name "Net-(U8-SW)") (class "Default")
      (node (ref "C20") (pin "2") (pinfunction "2_2") (pintype "input"))
      (node (ref "L2") (pin "1") (pinfunction "1_1") (pintype "input"))
      (node (ref "U8") (pin "5") (pinfunction "SW_5") (pintype "input"))
    )
    (net (code "39") (name "SCL_1") (class "Default")
      (node (ref "U2") (pin "1") (pinfunction "SCL/SPC_1") (pintype "input"))
      (node (ref "U6") (pin "10") (pinfunction "IO25_10") (pintype "input"))
    )
    (net (code "40") (name "SD0") (class "Default")
      (node (ref "U2") (pin "3") (pinfunction "SDO/SA0_3") (pintype "input"))
    )
    (net (code "41") (name "SDA_1") (class "Default")
      (node (ref "U2") (pin "4") (pinfunction "SDA/SDI/SDO_4") (pintype "input"))
      (node (ref "U6") (pin "11") (pinfunction "IO26_11") (pintype "input"))
    )
    (net (code "42") (name "S_A1") (class "Default")
      (node (ref "U3") (pin "8") (pinfunction "INPA_8") (pintype "input"))
      (node (ref "WB_IN_1") (pin "2") (pinfunction "2_2") (pintype "input"))
      (node (ref "WB_OUT_1") (pin "1") (pinfunction "1_1") (pintype "input"))
    )
    (net (code "43") (name "S_A2") (class "Default")
      (node (ref "U3") (pin "7") (pinfunction "INNA_7") (pintype "input"))
      (node (ref "WB_IN_2") (pin "1") (pinfunction "1_1") (pintype "input"))
      (node (ref "WB_OUT_2") (pin "2") (pinfunction "2_2") (pintype "input"))
    )
    (net (code "44") (name "S_AVDD") (class "Default")
      (node (ref "C4") (pin "2") (pinfunction "2_2") (pintype "input"))
      (node (ref "Q1") (pin "3") (pinfunction "C_3") (pintype "input"))
      (node (ref "R2") (pin "2") (pinfunction "2_2") (pintype "input"))
      (node (ref "U3") (pin "3") (pinfunction "AVDD_3") (pintype "input"))
      (node (ref "WB_OUT_1") (pin "2") (pinfunction "2_2") (pintype "input"))
      (node (ref "WB_OUT_2") (pin "1") (pinfunction "1_1") (pintype "input"))
    )
    (net (code "45") (name "S_BASE") (class "Default")
      (node (ref "Q1") (pin "1") (pinfunction "B_1") (pintype "input"))
      (node (ref "U3") (pin "2") (pinfunction "BASE_2") (pintype "input"))
    )
    (net (code "46") (name "S_DOUT") (class "Default")
      (node (ref "U3") (pin "12") (pinfunction "DOUT_12") (pintype "input"))
      (node (ref "U6") (pin "31") (pinfunction "IO19_31") (pintype "input"))
    )
    (net (code "47") (name "S_PD_SCK") (class "Default")
      (node (ref "U3") (pin "11") (pinfunction "PD_SCK_11") (pintype "input"))
      (node (ref "U6") (pin "30") (pinfunction "IO18_30") (pintype "input"))
    )
    (net (code "48") (name "S_VFB") (class "Default")
      (node (ref "R1") (pin "2") (pinfunction "2_2") (pintype "input"))
      (node (ref "R2") (pin "1") (pinfunction "1_1") (pintype "input"))
      (node (ref "U3") (pin "4") (pinfunction "VFB_4") (pintype "input"))
    )
    (net (code "49") (name "USB_CC1") (class "Default")
      (node (ref "R12") (pin "2") (pinfunction "2_2") (pintype "input"))
      (node (ref "USBC1") (pin "A5") (pinfunction "CC1_A5") (pintype "input"))
    )
    (net (code "50") (name "USB_CC2") (class "Default")
      (node (ref "R11") (pin "2") (pinfunction "2_2") (pintype "input"))
      (node (ref "USBC1") (pin "B5") (pinfunction "CC2_B5") (pintype "input"))
    )
    (net (code "51") (name "USB_D+") (class "Default")
      (node (ref "U5") (pin "4") (pinfunction "D+_4") (pintype "input"))
      (node (ref "USBC1") (pin "A6") (pinfunction "DP1_A6") (pintype "input"))
      (node (ref "USBC1") (pin "B6") (pinfunction "DP2_B6") (pintype "input"))
    )
    (net (code "52") (name "USB_D-") (class "Default")
      (node (ref "U5") (pin "5") (pinfunction "D-_5") (pintype "input"))
      (node (ref "USBC1") (pin "A7") (pinfunction "DN1_A7") (pintype "input"))
      (node (ref "USBC1") (pin "B7") (pinfunction "DN2_B7") (pintype "input"))
    )
    (net (code "53") (name "V_BUS") (class "Default")
      (node (ref "C10") (pin "2") (pinfunction "2_2") (pintype "input"))
      (node (ref "C11") (pin "2") (pinfunction "2_2") (pintype "input"))
      (node (ref "C16") (pin "1") (pinfunction "1_1") (pintype "input"))
      (node (ref "U5") (pin "7") (pinfunction "REGIN_7") (pintype "input"))
      (node (ref "U5") (pin "8") (pinfunction "VBUS_8") (pintype "input"))
      (node (ref "U7") (pin "3") (pinfunction "VIN_3") (pintype "input"))
      (node (ref "USBC1") (pin "A4") (pinfunction "VBUS_A4") (pintype "input"))
      (node (ref "USBC1") (pin "A9") (pinfunction "VBUS_A9") (pintype "input"))
      (node (ref "USBC1") (pin "B4") (pinfunction "VBUS_B4") (pintype "input"))
      (node (ref "USBC1") (pin "B9") (pinfunction "VBUS_B9") (pintype "input"))
    )
    (net (code "54") (name "unconnected-(LED1-DOU-Pad2)") (class "Default")
      (node (ref "LED1") (pin "2") (pinfunction "DOU_2") (pintype "input"))
    )
    (net (code "55") (name "unconnected-(LED3---Pad4)") (class "Default")
      (node (ref "LED3") (pin "4") (pinfunction "-_4") (pintype "input+no_connect"))
    )
    (net (code "56") (name "unconnected-(SW1-Pad1)") (class "Default")
      (node (ref "SW1") (pin "1") (pinfunction "1_1") (pintype "input"))
    )
    (net (code "57") (name "unconnected-(SW1-Pad4)") (class "Default")
      (node (ref "SW1") (pin "4") (pinfunction "4_4") (pintype "input"))
    )
    (net (code "58") (name "unconnected-(SW1-Pad5)") (class "Default")
      (node (ref "SW1") (pin "5") (pinfunction "5_5") (pintype "input"))
    )
    (net (code "59") (name "unconnected-(SW2-Pad3)") (class "Default")
      (node (ref "SW2") (pin "3") (pinfunction "3_3") (pintype "input"))
    )
    (net (code "60") (name "unconnected-(SW2-Pad4)") (class "Default")
      (node (ref "SW2") (pin "4") (pinfunction "4_4") (pintype "input"))
    )
    (net (code "61") (name "unconnected-(U2-NC-Pad5)") (class "Default")
      (node (ref "U2") (pin "5") (pinfunction "NC_5") (pintype "input+no_connect"))
    )
    (net (code "62") (name "unconnected-(U3-XO-Pad13)") (class "Default")
      (node (ref "U3") (pin "13") (pinfunction "XO_13") (pintype "input"))
    )
    (net (code "63") (name "unconnected-(U5-CTS-Pad23)") (class "Default")
      (node (ref "U5") (pin "23") (pinfunction "CTS_23") (pintype "input"))
    )
    (net (code "64") (name "unconnected-(U5-DCD-Pad1)") (class "Default")
      (node (ref "U5") (pin "1") (pinfunction "DCD_1") (pintype "input"))
    )
    (net (code "65") (name "unconnected-(U5-DSR-Pad27)") (class "Default")
      (node (ref "U5") (pin "27") (pinfunction "DSR_27") (pintype "input"))
    )
    (net (code "66") (name "unconnected-(U5-NC-Pad10)") (class "Default")
      (node (ref "U5") (pin "10") (pinfunction "NC_10") (pintype "input"))
    )
    (net (code "67") (name "unconnected-(U5-NC-Pad13)") (class "Default")
      (node (ref "U5") (pin "13") (pinfunction "NC_13") (pintype "input"))
    )
    (net (code "68") (name "unconnected-(U5-NC-Pad14)") (class "Default")
      (node (ref "U5") (pin "14") (pinfunction "NC_14") (pintype "input"))
    )
    (net (code "69") (name "unconnected-(U5-NC-Pad15)") (class "Default")
      (node (ref "U5") (pin "15") (pinfunction "NC_15") (pintype "input"))
    )
    (net (code "70") (name "unconnected-(U5-NC-Pad16)") (class "Default")
      (node (ref "U5") (pin "16") (pinfunction "NC_16") (pintype "input"))
    )
    (net (code "71") (name "unconnected-(U5-NC-Pad17)") (class "Default")
      (node (ref "U5") (pin "17") (pinfunction "NC_17") (pintype "input"))
    )
    (net (code "72") (name "unconnected-(U5-NC-Pad18)") (class "Default")
      (node (ref "U5") (pin "18") (pinfunction "NC_18") (pintype "input"))
    )
    (net (code "73") (name "unconnected-(U5-NC-Pad19)") (class "Default")
      (node (ref "U5") (pin "19") (pinfunction "NC_19") (pintype "input"))
    )
    (net (code "74") (name "unconnected-(U5-NC-Pad20)") (class "Default")
      (node (ref "U5") (pin "20") (pinfunction "NC_20") (pintype "input"))
    )
    (net (code "75") (name "unconnected-(U5-NC-Pad21)") (class "Default")
      (node (ref "U5") (pin "21") (pinfunction "NC_21") (pintype "input"))
    )
    (net (code "76") (name "unconnected-(U5-NC-Pad22)") (class "Default")
      (node (ref "U5") (pin "22") (pinfunction "NC_22") (pintype "input"))
    )
    (net (code "77") (name "unconnected-(U5-RI-Pad2)") (class "Default")
      (node (ref "U5") (pin "2") (pinfunction "RI_2") (pintype "input"))
    )
    (net (code "78") (name "unconnected-(U5-RST#-Pad9)") (class "Default")
      (node (ref "U5") (pin "9") (pinfunction "RST#_9") (pintype "input"))
    )
    (net (code "79") (name "unconnected-(U5-SUSPEND#-Pad11)") (class "Default")
      (node (ref "U5") (pin "11") (pinfunction "SUSPEND#_11") (pintype "input"))
    )
    (net (code "80") (name "unconnected-(U5-SUSPEND-Pad12)") (class "Default")
      (node (ref "U5") (pin "12") (pinfunction "SUSPEND_12") (pintype "input"))
    )
    (net (code "81") (name "unconnected-(U6-IO2-Pad24)") (class "Default")
      (node (ref "U6") (pin "24") (pinfunction "IO2_24") (pintype "input+no_connect"))
    )
    (net (code "82") (name "unconnected-(U6-IO4-Pad26)") (class "Default")
      (node (ref "U6") (pin "26") (pinfunction "IO4_26") (pintype "input"))
    )
    (net (code "83") (name "unconnected-(U6-IO5-Pad29)") (class "Default")
      (node (ref "U6") (pin "29") (pinfunction "IO5_29") (pintype "input"))
    )
    (net (code "84") (name "unconnected-(U6-IO13-Pad16)") (class "Default")
      (node (ref "U6") (pin "16") (pinfunction "IO13_16") (pintype "input"))
    )
    (net (code "85") (name "unconnected-(U6-IO15-Pad23)") (class "Default")
      (node (ref "U6") (pin "23") (pinfunction "IO15_23") (pintype "input"))
    )
    (net (code "86") (name "unconnected-(U6-IO21-Pad33)") (class "Default")
      (node (ref "U6") (pin "33") (pinfunction "IO21_33") (pintype "input"))
    )
    (net (code "87") (name "unconnected-(U6-IO22-Pad36)") (class "Default")
      (node (ref "U6") (pin "36") (pinfunction "IO22_36") (pintype "input"))
    )
    (net (code "88") (name "unconnected-(U6-IO23-Pad37)") (class "Default")
      (node (ref "U6") (pin "37") (pinfunction "IO23_37") (pintype "input"))
    )
    (net (code "89") (name "unconnected-(U6-NC-Pad17)") (class "Default")
      (node (ref "U6") (pin "17") (pinfunction "NC_17") (pintype "input+no_connect"))
    )
    (net (code "90") (name "unconnected-(U6-NC-Pad18)") (class "Default")
      (node (ref "U6") (pin "18") (pinfunction "NC_18") (pintype "input+no_connect"))
    )
    (net (code "91") (name "unconnected-(U6-NC-Pad19)") (class "Default")
      (node (ref "U6") (pin "19") (pinfunction "NC_19") (pintype "input+no_connect"))
    )
    (net (code "92") (name "unconnected-(U6-NC-Pad20)") (class "Default")
      (node (ref "U6") (pin "20") (pinfunction "NC_20") (pintype "input+no_connect"))
    )
    (net (code "93") (name "unconnected-(U6-NC-Pad21)") (class "Default")
      (node (ref "U6") (pin "21") (pinfunction "NC_21") (pintype "input+no_connect"))
    )
    (net (code "94") (name "unconnected-(U6-NC-Pad22)") (class "Default")
      (node (ref "U6") (pin "22") (pinfunction "NC_22") (pintype "input+no_connect"))
    )
    (net (code "95") (name "unconnected-(U6-NC-Pad32)") (class "Default")
      (node (ref "U6") (pin "32") (pinfunction "NC_32") (pintype "input+no_connect"))
    )
    (net (code "96") (name "unconnected-(U6-SENSOR_VN-Pad5)") (class "Default")
      (node (ref "U6") (pin "5") (pinfunction "SENSOR_VN_5") (pintype "input"))
    )
    (net (code "97") (name "unconnected-(U6-SENSOR_VP-Pad4)") (class "Default")
      (node (ref "U6") (pin "4") (pinfunction "SENSOR_VP_4") (pintype "input"))
    )
    (net (code "98") (name "unconnected-(USBC1-SBU1-PadA8)") (class "Default")
      (node (ref "USBC1") (pin "A8") (pinfunction "SBU1_A8") (pintype "input"))
    )
    (net (code "99") (name "unconnected-(USBC1-SBU2-PadB8)") (class "Default")
      (node (ref "USBC1") (pin "B8") (pinfunction "SBU2_B8") (pintype "input"))
    )
  )
)
